# MCU.net
KiCad netlist of a schematic drawn in Altium Designer
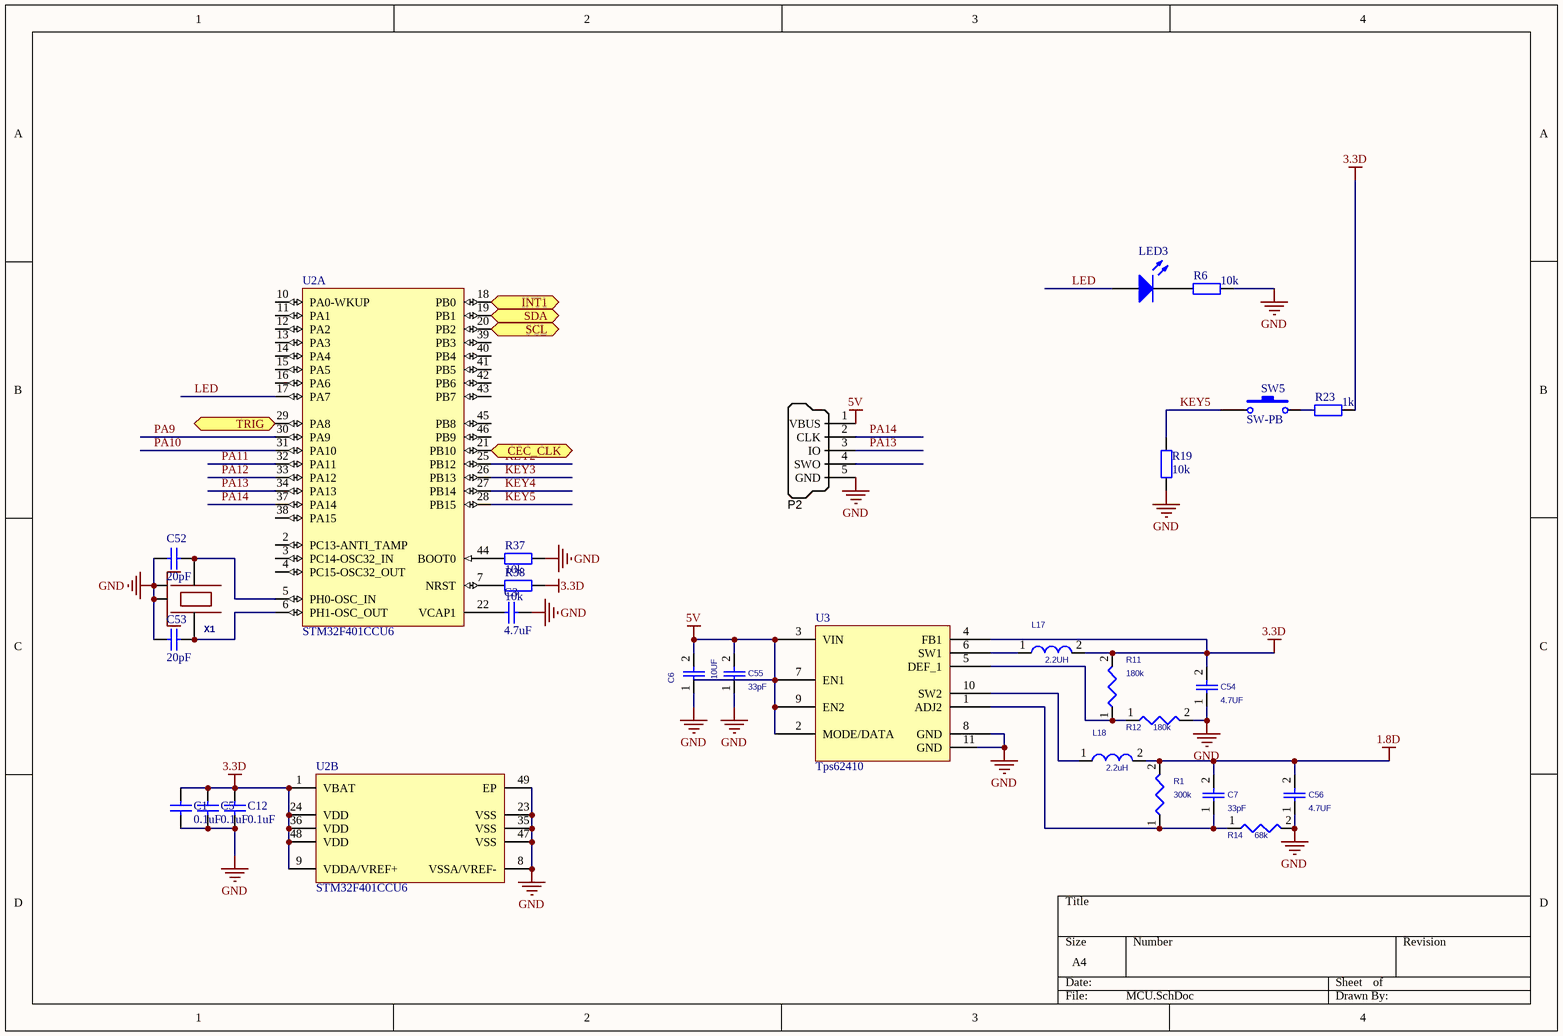
[diagram p0: MCU.SchDoc]

(export (version "E")
  (design (tool "Eeschema 10.0.6"))
  (components
    (comp (ref "C1")
      (value "0.1uF")
      (footprint "0402")
      (description "Capacitor")
      (fields (field (name "Comment") "Cap") (field (name "PUBLISHER") "Altium Limited"))
      (libsource (lib "RTC6705") (part "Cap"))
    )
    (comp (ref "C3")
      (value "4.7uF")
      (footprint "0603")
      (description "Capacitor")
      (fields (field (name "Comment") "Cap") (field (name "PUBLISHER") "Altium Limited"))
      (libsource (lib "RTC6705") (part "Cap"))
    )
    (comp (ref "C5")
      (value "0.1uF")
      (footprint "0402")
      (description "Capacitor")
      (fields (field (name "Comment") "Cap") (field (name "PUBLISHER") "Altium Limited"))
      (libsource (lib "RTC6705") (part "Cap"))
    )
    (comp (ref "C6") (value "10UF") (footprint "0805") (libsource (lib "*") (part "CAP/0402")))
    (comp (ref "C7") (value "33pF") (footprint "0402") (libsource (lib "*") (part "CAP/0402")))
    (comp (ref "C12")
      (value "0.1uF")
      (footprint "0402")
      (description "Capacitor")
      (fields (field (name "Comment") "Cap") (field (name "PUBLISHER") "Altium Limited"))
      (libsource (lib "RTC6705") (part "Cap"))
    )
    (comp (ref "C52")
      (value "20pF")
      (footprint "0402")
      (description "Capacitor")
      (fields (field (name "Comment") "Cap") (field (name "PUBLISHER") "Altium Limited"))
      (libsource (lib "RTC6705") (part "Cap"))
    )
    (comp (ref "C53")
      (value "20pF")
      (footprint "0402")
      (description "Capacitor")
      (fields (field (name "Comment") "Cap") (field (name "PUBLISHER") "Altium Limited"))
      (libsource (lib "RTC6705") (part "Cap"))
    )
    (comp (ref "C54") (value "4.7UF") (footprint "0805") (libsource (lib "*") (part "CAP/0402")))
    (comp (ref "C55") (value "33pF") (footprint "0603L") (libsource (lib "*") (part "CAP/0402")))
    (comp (ref "C56") (value "4.7UF") (footprint "0805") (libsource (lib "*") (part "CAP/0402")))
    (comp (ref "L17") (value "2.2UH") (footprint "0806") (libsource (lib "*") (part "L/2.5*2.0")))
    (comp (ref "L18") (value "2.2uH") (footprint "0806") (libsource (lib "*") (part "L/2.5*2.0")))
    (comp (ref "LED3")
      (value "LED0")
      (footprint "0603")
      (description "Typical INFRARED GaAs LED")
      (fields (field (name "PUBLISHER") "Altium Limited"))
      (libsource (lib "Miscellaneous Devices") (part "LED0"))
    )
    (comp (ref "P2")
      (value "SWD_MicroUSB")
      (footprint "MICRO-YZX")
      (description "Connector SMD USB Micro Type B middle mount")
      (libsource (lib "sch") (part "SWD_MicroUSB"))
    )
    (comp (ref "R1") (value "300k") (footprint "0402") (libsource (lib "*") (part "RES/0402_3")))
    (comp (ref "R6")
      (value "10k")
      (footprint "0402")
      (description "Resistor")
      (fields (field (name "PUBLISHER") "Altium Limited"))
      (libsource (lib "") (part "Res2_1"))
    )
    (comp (ref "R11") (value "180k") (footprint "0402") (libsource (lib "*") (part "RES/0402_3")))
    (comp (ref "R12") (value "180k") (footprint "0402") (libsource (lib "*") (part "RES/0402_3")))
    (comp (ref "R14") (value "68k") (footprint "0402") (libsource (lib "*") (part "RES/0402_3")))
    (comp (ref "R19")
      (value "10k")
      (footprint "0402")
      (description "Resistor")
      (fields (field (name "PUBLISHER") "Altium Limited"))
      (libsource (lib "Miscellaneous Devices") (part "Res2"))
    )
    (comp (ref "R23")
      (value "1k")
      (footprint "0402")
      (description "Resistor")
      (fields (field (name "PUBLISHER") "Altium Limited"))
      (libsource (lib "") (part "Res2_1"))
    )
    (comp (ref "R37")
      (value "10k")
      (footprint "0402")
      (description "Resistor")
      (fields (field (name "Comment") "Res2") (field (name "PUBLISHER") "Altium Limited"))
      (libsource (lib "") (part "Res2_1"))
    )
    (comp (ref "R38")
      (value "10k")
      (footprint "0402")
      (description "Resistor")
      (fields (field (name "Comment") "Res2") (field (name "PUBLISHER") "Altium Limited"))
      (libsource (lib "RTC6705") (part "Res2"))
    )
    (comp (ref "SW5")
      (value "SW-PB")
      (footprint "SW3x4")
      (description "Switch")
      (fields (field (name "PUBLISHER") "Altium Limited"))
      (libsource (lib "Miscellaneous Devices") (part "SW-PB"))
    )
    (comp (ref "U2")
      (value "STM32F401CCU6")
      (footprint "STM-UFQFPN48_N")
      (fields (field (name "MANUFACTURER") "STMicroelectronics"))
      (libsource (lib "STMicroelectronics STM32 F4") (part "STM32F401CCU6"))
    )
    (comp (ref "U3") (value "Tps62410") (footprint "DFN-10P-3X3") (libsource (lib "Euler") (part "Tps62410")))
    (comp (ref "X1")
      (value "24.000 KHz 3.2x2.5mm 8-10pf")
      (footprint "OSCILLATOR-3.2X2.5")
      (description "Crystal Oscillator in 3.2x2.5 SMD")
      (libsource (lib "pixhawk2") (part "OSCILLATOR-3.2X2.5"))
    )
  )
  (nets
    (net (code "1") (name "/CEC_CLK") (class "Default")
      (node (ref "U2") (pin "21") (pinfunction "PB10_21") (pintype "bidirectional"))
    )
    (net (code "2") (name "/INT1") (class "Default")
      (node (ref "U2") (pin "18") (pinfunction "PB0_18") (pintype "bidirectional"))
    )
    (net (code "3") (name "/KEY2") (class "Default")
      (node (ref "U2") (pin "25") (pinfunction "PB12_25") (pintype "bidirectional"))
    )
    (net (code "4") (name "/KEY3") (class "Default")
      (node (ref "U2") (pin "26") (pinfunction "PB13_26") (pintype "bidirectional"))
    )
    (net (code "5") (name "/KEY4") (class "Default")
      (node (ref "U2") (pin "27") (pinfunction "PB14_27") (pintype "bidirectional"))
    )
    (net (code "6") (name "/KEY5") (class "Default")
      (node (ref "R19") (pin "2") (pinfunction "2_2") (pintype "passive"))
      (node (ref "SW5") (pin "1") (pinfunction "1_1") (pintype "passive"))
      (node (ref "U2") (pin "28") (pinfunction "PB15_28") (pintype "bidirectional"))
    )
    (net (code "7") (name "/LED") (class "Default")
      (node (ref "LED3") (pin "1") (pinfunction "A_1") (pintype "passive"))
      (node (ref "U2") (pin "17") (pinfunction "PA7_17") (pintype "bidirectional"))
    )
    (net (code "8") (name "/PA9") (class "Default")
      (node (ref "U2") (pin "30") (pinfunction "PA9_30") (pintype "bidirectional"))
    )
    (net (code "9") (name "/PA10") (class "Default")
      (node (ref "U2") (pin "31") (pinfunction "PA10_31") (pintype "bidirectional"))
    )
    (net (code "10") (name "/PA11") (class "Default")
      (node (ref "U2") (pin "32") (pinfunction "PA11_32") (pintype "bidirectional"))
    )
    (net (code "11") (name "/PA12") (class "Default")
      (node (ref "U2") (pin "33") (pinfunction "PA12_33") (pintype "bidirectional"))
    )
    (net (code "12") (name "/PA13") (class "Default")
      (node (ref "P2") (pin "3") (pinfunction "IO_3") (pintype "passive"))
      (node (ref "U2") (pin "34") (pinfunction "PA13_34") (pintype "bidirectional"))
    )
    (net (code "13") (name "/PA14") (class "Default")
      (node (ref "P2") (pin "2") (pinfunction "CLK_2") (pintype "passive"))
      (node (ref "U2") (pin "37") (pinfunction "PA14_37") (pintype "bidirectional"))
    )
    (net (code "14") (name "/SCL") (class "Default")
      (node (ref "U2") (pin "20") (pinfunction "PB2_20") (pintype "bidirectional"))
    )
    (net (code "15") (name "/SDA") (class "Default")
      (node (ref "U2") (pin "19") (pinfunction "PB1_19") (pintype "bidirectional"))
    )
    (net (code "16") (name "/TRIG") (class "Default")
      (node (ref "U2") (pin "29") (pinfunction "PA8_29") (pintype "bidirectional"))
    )
    (net (code "17") (name "1.8D") (class "Default")
      (node (ref "C56") (pin "2") (pinfunction "2_2") (pintype "passive"))
      (node (ref "C7") (pin "2") (pinfunction "2_2") (pintype "passive"))
      (node (ref "L18") (pin "2") (pinfunction "2_2") (pintype "passive"))
      (node (ref "R1") (pin "2") (pinfunction "2_2") (pintype "passive"))
    )
    (net (code "18") (name "3.3D") (class "Default")
      (node (ref "C1") (pin "2") (pinfunction "2_2") (pintype "passive"))
      (node (ref "C12") (pin "2") (pinfunction "2_2") (pintype "passive"))
      (node (ref "C5") (pin "2") (pinfunction "2_2") (pintype "passive"))
      (node (ref "C54") (pin "2") (pinfunction "2_2") (pintype "passive"))
      (node (ref "L17") (pin "2") (pinfunction "2_2") (pintype "passive"))
      (node (ref "R11") (pin "2") (pinfunction "2_2") (pintype "passive"))
      (node (ref "R23") (pin "2") (pinfunction "2_2") (pintype "passive"))
      (node (ref "R38") (pin "1") (pinfunction "1_1") (pintype "passive"))
      (node (ref "U2") (pin "1") (pinfunction "VBAT_1") (pintype "power_in"))
      (node (ref "U2") (pin "24") (pinfunction "VDD_24") (pintype "power_in"))
      (node (ref "U2") (pin "36") (pinfunction "VDD_36") (pintype "power_in"))
      (node (ref "U2") (pin "48") (pinfunction "VDD_48") (pintype "power_in"))
      (node (ref "U2") (pin "9") (pinfunction "VDDA/VREF+_9") (pintype "power_in"))
      (node (ref "U3") (pin "4") (pinfunction "FB1_4") (pintype "passive"))
    )
    (net (code "19") (name "5V") (class "Default")
      (node (ref "C55") (pin "2") (pinfunction "2_2") (pintype "passive"))
      (node (ref "C6") (pin "2") (pinfunction "2_2") (pintype "passive"))
      (node (ref "P2") (pin "1") (pinfunction "VBUS_1") (pintype "passive"))
      (node (ref "U3") (pin "2") (pinfunction "MODE/DATA_2") (pintype "passive"))
      (node (ref "U3") (pin "3") (pinfunction "VIN_3") (pintype "passive"))
      (node (ref "U3") (pin "7") (pinfunction "EN1_7") (pintype "passive"))
      (node (ref "U3") (pin "9") (pinfunction "EN2_9") (pintype "passive"))
    )
    (net (code "20") (name "GND") (class "Default")
      (node (ref "C1") (pin "1") (pinfunction "1_1") (pintype "passive"))
      (node (ref "C12") (pin "1") (pinfunction "1_1") (pintype "passive"))
      (node (ref "C3") (pin "1") (pinfunction "1_1") (pintype "passive"))
      (node (ref "C5") (pin "1") (pinfunction "1_1") (pintype "passive"))
      (node (ref "C52") (pin "1") (pinfunction "1_1") (pintype "passive"))
      (node (ref "C53") (pin "1") (pinfunction "1_1") (pintype "passive"))
      (node (ref "C54") (pin "1") (pinfunction "1_1") (pintype "passive"))
      (node (ref "C55") (pin "1") (pinfunction "1_1") (pintype "passive"))
      (node (ref "C56") (pin "1") (pinfunction "1_1") (pintype "passive"))
      (node (ref "C6") (pin "1") (pinfunction "1_1") (pintype "passive"))
      (node (ref "P2") (pin "5") (pinfunction "GND_5") (pintype "passive"))
      (node (ref "R12") (pin "2") (pinfunction "2_2") (pintype "passive"))
      (node (ref "R14") (pin "2") (pinfunction "2_2") (pintype "passive"))
      (node (ref "R19") (pin "1") (pinfunction "1_1") (pintype "passive"))
      (node (ref "R37") (pin "2") (pinfunction "2_2") (pintype "passive"))
      (node (ref "R6") (pin "2") (pinfunction "2_2") (pintype "passive"))
      (node (ref "U2") (pin "23") (pinfunction "VSS_23") (pintype "power_in"))
      (node (ref "U2") (pin "35") (pinfunction "VSS_35") (pintype "power_in"))
      (node (ref "U2") (pin "47") (pinfunction "VSS_47") (pintype "power_in"))
      (node (ref "U2") (pin "49") (pinfunction "EP_49") (pintype "power_in"))
      (node (ref "U2") (pin "8") (pinfunction "VSSA/VREF-_8") (pintype "power_in"))
      (node (ref "U3") (pin "11") (pinfunction "GND_11") (pintype "passive"))
      (node (ref "U3") (pin "8") (pinfunction "GND_8") (pintype "passive"))
      (node (ref "X1") (pin "2") (pinfunction "NC_2_2") (pintype "open_emitter"))
      (node (ref "X1") (pin "4") (pinfunction "NC_4_4") (pintype "open_emitter"))
    )
    (net (code "21") (name "Net-(LED3-K)") (class "Default")
      (node (ref "LED3") (pin "2") (pinfunction "K_2") (pintype "passive"))
      (node (ref "R6") (pin "1") (pinfunction "1_1") (pintype "passive"))
    )
    (net (code "22") (name "Net-(R23-Pad1)") (class "Default")
      (node (ref "R23") (pin "1") (pinfunction "1_1") (pintype "passive"))
      (node (ref "SW5") (pin "2") (pinfunction "2_2") (pintype "passive"))
    )
    (net (code "23") (name "Net-(U2A-BOOT0)") (class "Default")
      (node (ref "R37") (pin "1") (pinfunction "1_1") (pintype "passive"))
      (node (ref "U2") (pin "44") (pinfunction "BOOT0_44") (pintype "input"))
    )
    (net (code "24") (name "Net-(U2A-NRST)") (class "Default")
      (node (ref "R38") (pin "2") (pinfunction "2_2") (pintype "passive"))
      (node (ref "U2") (pin "7") (pinfunction "NRST_7") (pintype "bidirectional"))
    )
    (net (code "25") (name "Net-(U2A-PH0-OSC_IN)") (class "Default")
      (node (ref "C52") (pin "2") (pinfunction "2_2") (pintype "passive"))
      (node (ref "U2") (pin "5") (pinfunction "PH0-OSC_IN_5") (pintype "bidirectional"))
      (node (ref "X1") (pin "1") (pinfunction "1_1") (pintype "passive"))
    )
    (net (code "26") (name "Net-(U2A-PH1-OSC_OUT)") (class "Default")
      (node (ref "C53") (pin "2") (pinfunction "2_2") (pintype "passive"))
      (node (ref "U2") (pin "6") (pinfunction "PH1-OSC_OUT_6") (pintype "bidirectional"))
      (node (ref "X1") (pin "3") (pinfunction "3_3") (pintype "passive"))
    )
    (net (code "27") (name "Net-(U2A-VCAP1)") (class "Default")
      (node (ref "C3") (pin "2") (pinfunction "2_2") (pintype "passive"))
      (node (ref "U2") (pin "22") (pinfunction "VCAP1_22") (pintype "power_in"))
    )
    (net (code "28") (name "Net-(U3-ADJ2)") (class "Default")
      (node (ref "C7") (pin "1") (pinfunction "1_1") (pintype "passive"))
      (node (ref "R1") (pin "1") (pinfunction "1_1") (pintype "passive"))
      (node (ref "R14") (pin "1") (pinfunction "1_1") (pintype "passive"))
      (node (ref "U3") (pin "1") (pinfunction "ADJ2_1") (pintype "passive"))
    )
    (net (code "29") (name "Net-(U3-DEF_1)") (class "Default")
      (node (ref "R11") (pin "1") (pinfunction "1_1") (pintype "passive"))
      (node (ref "R12") (pin "1") (pinfunction "1_1") (pintype "passive"))
      (node (ref "U3") (pin "5") (pinfunction "DEF_1_5") (pintype "passive"))
    )
    (net (code "30") (name "Net-(U3-SW1)") (class "Default")
      (node (ref "L17") (pin "1") (pinfunction "1_1") (pintype "passive"))
      (node (ref "U3") (pin "6") (pinfunction "SW1_6") (pintype "passive"))
    )
    (net (code "31") (name "Net-(U3-SW2)") (class "Default")
      (node (ref "L18") (pin "1") (pinfunction "1_1") (pintype "passive"))
      (node (ref "U3") (pin "10") (pinfunction "SW2_10") (pintype "passive"))
    )
    (net (code "32") (name "unconnected-(P2-SWO-Pad4)") (class "Default")
      (node (ref "P2") (pin "4") (pinfunction "SWO_4") (pintype "passive"))
    )
    (net (code "33") (name "unconnected-(U2A-PA0-WKUP-Pad10)") (class "Default")
      (node (ref "U2") (pin "10") (pinfunction "PA0-WKUP_10") (pintype "bidirectional"))
    )
    (net (code "34") (name "unconnected-(U2A-PA1-Pad11)") (class "Default")
      (node (ref "U2") (pin "11") (pinfunction "PA1_11") (pintype "bidirectional"))
    )
    (net (code "35") (name "unconnected-(U2A-PA2-Pad12)") (class "Default")
      (node (ref "U2") (pin "12") (pinfunction "PA2_12") (pintype "bidirectional"))
    )
    (net (code "36") (name "unconnected-(U2A-PA3-Pad13)") (class "Default")
      (node (ref "U2") (pin "13") (pinfunction "PA3_13") (pintype "bidirectional"))
    )
    (net (code "37") (name "unconnected-(U2A-PA4-Pad14)") (class "Default")
      (node (ref "U2") (pin "14") (pinfunction "PA4_14") (pintype "bidirectional"))
    )
    (net (code "38") (name "unconnected-(U2A-PA5-Pad15)") (class "Default")
      (node (ref "U2") (pin "15") (pinfunction "PA5_15") (pintype "bidirectional"))
    )
    (net (code "39") (name "unconnected-(U2A-PA6-Pad16)") (class "Default")
      (node (ref "U2") (pin "16") (pinfunction "PA6_16") (pintype "bidirectional"))
    )
    (net (code "40") (name "unconnected-(U2A-PA15-Pad38)") (class "Default")
      (node (ref "U2") (pin "38") (pinfunction "PA15_38") (pintype "bidirectional"))
    )
    (net (code "41") (name "unconnected-(U2A-PB3-Pad39)") (class "Default")
      (node (ref "U2") (pin "39") (pinfunction "PB3_39") (pintype "bidirectional"))
    )
    (net (code "42") (name "unconnected-(U2A-PB4-Pad40)") (class "Default")
      (node (ref "U2") (pin "40") (pinfunction "PB4_40") (pintype "bidirectional"))
    )
    (net (code "43") (name "unconnected-(U2A-PB5-Pad41)") (class "Default")
      (node (ref "U2") (pin "41") (pinfunction "PB5_41") (pintype "bidirectional"))
    )
    (net (code "44") (name "unconnected-(U2A-PB6-Pad42)") (class "Default")
      (node (ref "U2") (pin "42") (pinfunction "PB6_42") (pintype "bidirectional"))
    )
    (net (code "45") (name "unconnected-(U2A-PB7-Pad43)") (class "Default")
      (node (ref "U2") (pin "43") (pinfunction "PB7_43") (pintype "bidirectional"))
    )
    (net (code "46") (name "unconnected-(U2A-PB8-Pad45)") (class "Default")
      (node (ref "U2") (pin "45") (pinfunction "PB8_45") (pintype "bidirectional"))
    )
    (net (code "47") (name "unconnected-(U2A-PB9-Pad46)") (class "Default")
      (node (ref "U2") (pin "46") (pinfunction "PB9_46") (pintype "bidirectional"))
    )
    (net (code "48") (name "unconnected-(U2A-PC13-ANTI_TAMP-Pad2)") (class "Default")
      (node (ref "U2") (pin "2") (pinfunction "PC13-ANTI_TAMP_2") (pintype "bidirectional"))
    )
    (net (code "49") (name "unconnected-(U2A-PC14-OSC32_IN-Pad3)") (class "Default")
      (node (ref "U2") (pin "3") (pinfunction "PC14-OSC32_IN_3") (pintype "bidirectional"))
    )
    (net (code "50") (name "unconnected-(U2A-PC15-OSC32_OUT-Pad4)") (class "Default")
      (node (ref "U2") (pin "4") (pinfunction "PC15-OSC32_OUT_4") (pintype "bidirectional"))
    )
  )
)
